# RS232_IrDA.net
KiCad netlist of a schematic drawn in Altium Designer
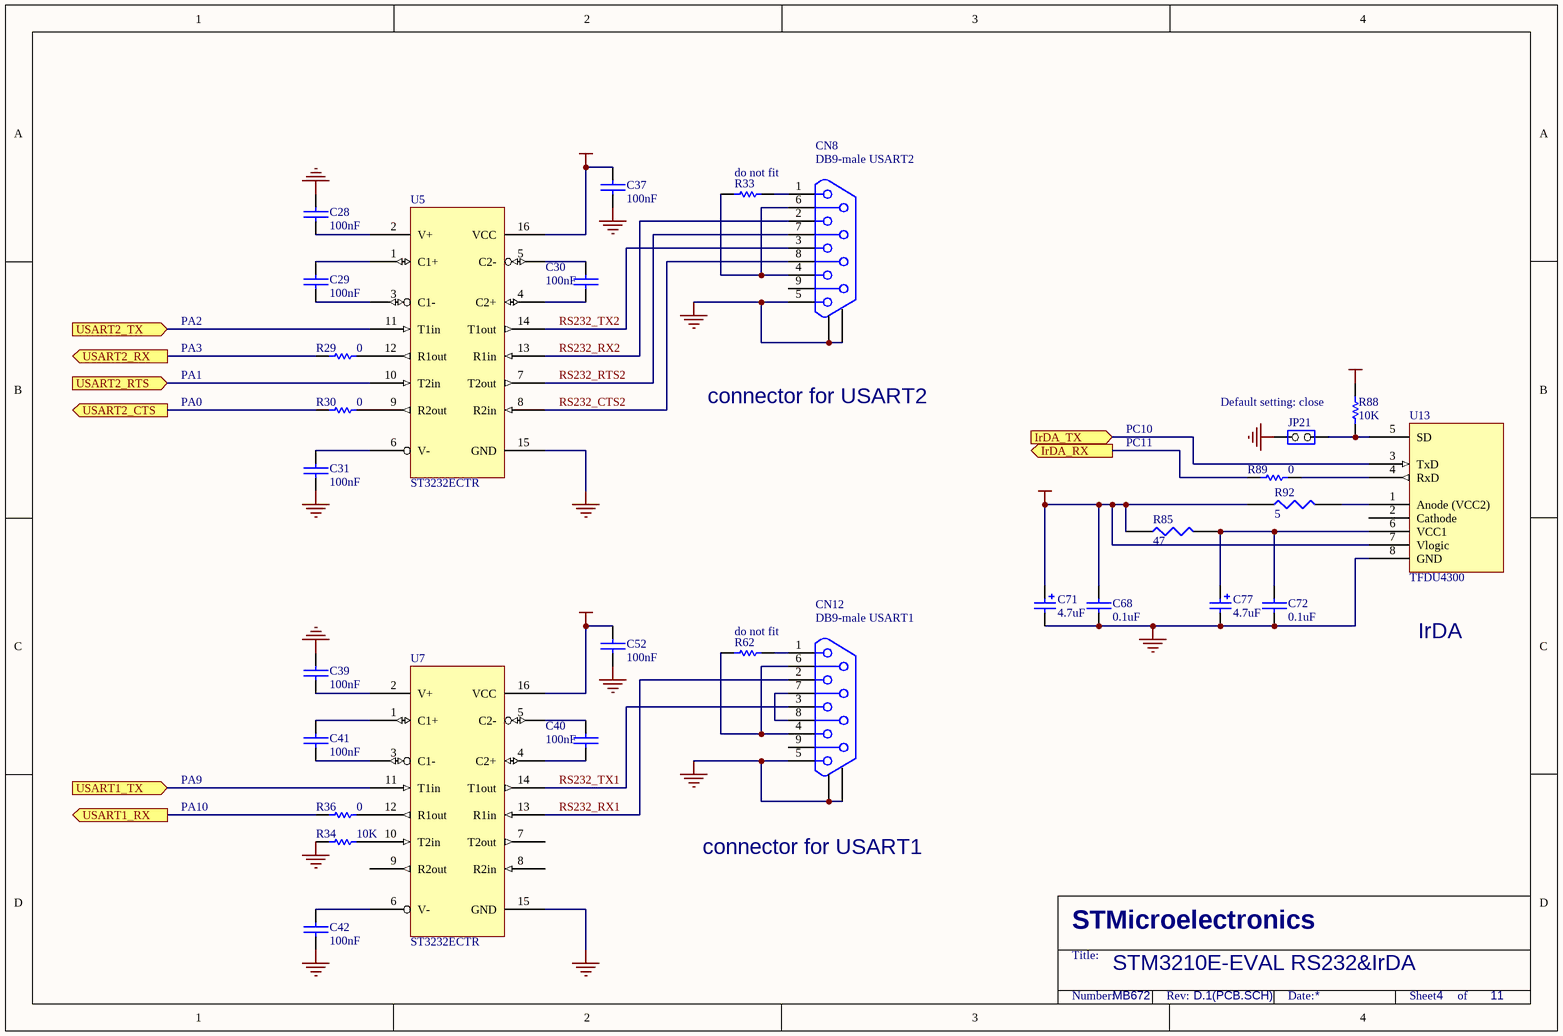
[diagram p0: RS232&IrDA.SchDoc]

(export (version "E")
  (design (tool "Eeschema 10.0.6"))
  (components
    (comp (ref "C28")
      (value "100nF")
      (footprint "0603P")
      (description "Capacitor")
      (libsource (lib "*") (part "CAP"))
    )
    (comp (ref "C29")
      (value "100nF")
      (footprint "0603P")
      (description "Capacitor")
      (libsource (lib "*") (part "CAP"))
    )
    (comp (ref "C30")
      (value "100nF")
      (footprint "0603P")
      (description "Capacitor")
      (libsource (lib "*") (part "CAP"))
    )
    (comp (ref "C31")
      (value "100nF")
      (footprint "0603P")
      (description "Capacitor")
      (libsource (lib "*") (part "CAP"))
    )
    (comp (ref "C37")
      (value "100nF")
      (footprint "0603P")
      (description "Capacitor")
      (libsource (lib "*") (part "CAP"))
    )
    (comp (ref "C39")
      (value "100nF")
      (footprint "0603P")
      (description "Capacitor")
      (libsource (lib "*") (part "CAP"))
    )
    (comp (ref "C40")
      (value "100nF")
      (footprint "0603P")
      (description "Capacitor")
      (libsource (lib "*") (part "CAP"))
    )
    (comp (ref "C41")
      (value "100nF")
      (footprint "0603P")
      (description "Capacitor")
      (libsource (lib "*") (part "CAP"))
    )
    (comp (ref "C42")
      (value "100nF")
      (footprint "0603P")
      (description "Capacitor")
      (libsource (lib "*") (part "CAP"))
    )
    (comp (ref "C52")
      (value "100nF")
      (footprint "0603P")
      (description "Capacitor")
      (libsource (lib "*") (part "CAP"))
    )
    (comp (ref "C68")
      (value "0.1uF")
      (footprint "0603P")
      (description "Capacitor")
      (libsource (lib "*") (part "CAP"))
    )
    (comp (ref "C71")
      (value "4.7uF")
      (footprint "TAN-B")
      (description "Polarized Capacitor (Radial)")
      (fields (field (name "PUBLISHER") "Altium Limited"))
      (libsource (lib "Miscellaneous Devices") (part "Cap Pol1"))
    )
    (comp (ref "C72")
      (value "0.1uF")
      (footprint "0603P")
      (description "Capacitor")
      (libsource (lib "*") (part "CAP"))
    )
    (comp (ref "C77")
      (value "4.7uF")
      (footprint "TAN-B")
      (description "Polarized Capacitor (Radial)")
      (fields (field (name "PUBLISHER") "Altium Limited"))
      (libsource (lib "Miscellaneous Devices") (part "Cap Pol1"))
    )
    (comp (ref "CN8") (value "DB9-male USART2") (footprint "DB9/M") (libsource (lib "*") (part "DB9")))
    (comp (ref "CN12") (value "DB9-male USART1") (footprint "DB9/M") (libsource (lib "*") (part "DB9")))
    (comp (ref "JP21") (value "~") (footprint "SIP2") (libsource (lib "*") (part "JP2")))
    (comp (ref "R29")
      (value "0")
      (description "Resistor")
      (fields (field (name "PUBLISHER") "Altium Limited"))
      (libsource (lib "Miscellaneous Devices") (part "Res1"))
    )
    (comp (ref "R30")
      (value "0")
      (description "Resistor")
      (fields (field (name "PUBLISHER") "Altium Limited"))
      (libsource (lib "Miscellaneous Devices") (part "Res1"))
    )
    (comp (ref "R33")
      (value "do not fit")
      (footprint "0603_NC")
      (description "Resistor")
      (fields (field (name "PUBLISHER") "Altium Limited"))
      (libsource (lib "Miscellaneous Devices") (part "res1"))
    )
    (comp (ref "R34")
      (value "10K")
      (description "Resistor")
      (fields (field (name "PUBLISHER") "Altium Limited"))
      (libsource (lib "Miscellaneous Devices") (part "Res1"))
    )
    (comp (ref "R36")
      (value "0")
      (description "Resistor")
      (fields (field (name "PUBLISHER") "Altium Limited"))
      (libsource (lib "Miscellaneous Devices") (part "Res1"))
    )
    (comp (ref "R62")
      (value "do not fit")
      (footprint "0603_NC")
      (description "Resistor")
      (fields (field (name "PUBLISHER") "Altium Limited"))
      (libsource (lib "Miscellaneous Devices") (part "res1"))
    )
    (comp (ref "R85") (value "47") (footprint "0603") (libsource (lib "*") (part "RES1")))
    (comp (ref "R88")
      (value "10K")
      (description "Resistor")
      (fields (field (name "PUBLISHER") "Altium Limited"))
      (libsource (lib "Miscellaneous Devices") (part "Res1"))
    )
    (comp (ref "R89")
      (value "0")
      (description "Resistor")
      (fields (field (name "PUBLISHER") "Altium Limited"))
      (libsource (lib "Miscellaneous Devices") (part "Res1"))
    )
    (comp (ref "R92") (value "5") (footprint "0603") (libsource (lib "*") (part "RES1")))
    (comp (ref "U5")
      (value "ST3232ECTR")
      (footprint "TSSOP16")
      (description "3.3V/5V Dual RS232 Transceiver w/ Int. Cap.")
      (libsource (lib "*") (part "ST3232"))
    )
    (comp (ref "U7")
      (value "ST3232ECTR")
      (footprint "TSSOP16")
      (description "3.3V/5V Dual RS232 Transceiver w/ Int. Cap.")
      (libsource (lib "*") (part "ST3232"))
    )
    (comp (ref "U13") (value "TFDU4300") (footprint "IR_VISHAY3") (libsource (lib "*") (part "TFDU4300")))
  )
  (nets
    (net (code "1") (name "+3V3") (class "Default")
      (node (ref "C37") (pin "1") (pinfunction "1_1") (pintype "passive"))
      (node (ref "C52") (pin "1") (pinfunction "1_1") (pintype "passive"))
      (node (ref "C68") (pin "1") (pinfunction "1_1") (pintype "passive"))
      (node (ref "C71") (pin "1") (pinfunction "1_1") (pintype "passive"))
      (node (ref "R85") (pin "1") (pinfunction "1_1") (pintype "passive"))
      (node (ref "R88") (pin "2") (pinfunction "2_2") (pintype "passive"))
      (node (ref "R92") (pin "1") (pinfunction "1_1") (pintype "passive"))
      (node (ref "U13") (pin "7") (pinfunction "Vlogic_7") (pintype "passive"))
      (node (ref "U5") (pin "16") (pinfunction "VCC_16") (pintype "passive"))
      (node (ref "U7") (pin "16") (pinfunction "VCC_16") (pintype "passive"))
    )
    (net (code "2") (name "/IrDA_RX") (class "Default")
      (node (ref "R89") (pin "2") (pinfunction "2_2") (pintype "passive"))
    )
    (net (code "3") (name "/IrDA_TX") (class "Default")
      (node (ref "U13") (pin "3") (pinfunction "TxD_3") (pintype "input"))
    )
    (net (code "4") (name "/RS232_CTS2") (class "Default")
      (node (ref "CN8") (pin "8") (pinfunction "8_8") (pintype "passive"))
      (node (ref "U5") (pin "8") (pinfunction "R2in_8") (pintype "input"))
    )
    (net (code "5") (name "/RS232_RTS2") (class "Default")
      (node (ref "CN8") (pin "7") (pinfunction "7_7") (pintype "passive"))
      (node (ref "U5") (pin "7") (pinfunction "T2out_7") (pintype "output"))
    )
    (net (code "6") (name "/RS232_RX1") (class "Default")
      (node (ref "CN12") (pin "2") (pinfunction "2_2") (pintype "passive"))
      (node (ref "U7") (pin "13") (pinfunction "R1in_13") (pintype "input"))
    )
    (net (code "7") (name "/RS232_RX2") (class "Default")
      (node (ref "CN8") (pin "2") (pinfunction "2_2") (pintype "passive"))
      (node (ref "U5") (pin "13") (pinfunction "R1in_13") (pintype "input"))
    )
    (net (code "8") (name "/RS232_TX1") (class "Default")
      (node (ref "CN12") (pin "3") (pinfunction "3_3") (pintype "passive"))
      (node (ref "U7") (pin "14") (pinfunction "T1out_14") (pintype "output"))
    )
    (net (code "9") (name "/RS232_TX2") (class "Default")
      (node (ref "CN8") (pin "3") (pinfunction "3_3") (pintype "passive"))
      (node (ref "U5") (pin "14") (pinfunction "T1out_14") (pintype "output"))
    )
    (net (code "10") (name "/USART1_RX") (class "Default")
      (node (ref "R36") (pin "2") (pinfunction "2_2") (pintype "passive"))
    )
    (net (code "11") (name "/USART1_TX") (class "Default")
      (node (ref "U7") (pin "11") (pinfunction "T1in_11") (pintype "input"))
    )
    (net (code "12") (name "/USART2_CTS") (class "Default")
      (node (ref "R30") (pin "2") (pinfunction "2_2") (pintype "passive"))
    )
    (net (code "13") (name "/USART2_RTS") (class "Default")
      (node (ref "U5") (pin "10") (pinfunction "T2in_10") (pintype "input"))
    )
    (net (code "14") (name "/USART2_RX") (class "Default")
      (node (ref "R29") (pin "2") (pinfunction "2_2") (pintype "passive"))
    )
    (net (code "15") (name "/USART2_TX") (class "Default")
      (node (ref "U5") (pin "11") (pinfunction "T1in_11") (pintype "input"))
    )
    (net (code "16") (name "GND") (class "Default")
      (node (ref "C28") (pin "1") (pinfunction "1_1") (pintype "passive"))
      (node (ref "C31") (pin "1") (pinfunction "1_1") (pintype "passive"))
      (node (ref "C37") (pin "2") (pinfunction "2_2") (pintype "passive"))
      (node (ref "C39") (pin "1") (pinfunction "1_1") (pintype "passive"))
      (node (ref "C42") (pin "1") (pinfunction "1_1") (pintype "passive"))
      (node (ref "C52") (pin "2") (pinfunction "2_2") (pintype "passive"))
      (node (ref "C68") (pin "2") (pinfunction "2_2") (pintype "passive"))
      (node (ref "C71") (pin "2") (pinfunction "2_2") (pintype "passive"))
      (node (ref "C72") (pin "2") (pinfunction "2_2") (pintype "passive"))
      (node (ref "C77") (pin "2") (pinfunction "2_2") (pintype "passive"))
      (node (ref "CN12") (pin "0") (pinfunction "10_0") (pintype "passive"))
      (node (ref "CN12") (pin "5") (pinfunction "5_5") (pintype "passive"))
      (node (ref "CN8") (pin "0") (pinfunction "10_0") (pintype "passive"))
      (node (ref "CN8") (pin "5") (pinfunction "5_5") (pintype "passive"))
      (node (ref "JP21") (pin "2") (pinfunction "NO_2") (pintype "passive"))
      (node (ref "R34") (pin "2") (pinfunction "2_2") (pintype "passive"))
      (node (ref "U13") (pin "8") (pinfunction "GND_8") (pintype "passive"))
      (node (ref "U5") (pin "15") (pinfunction "GND_15") (pintype "passive"))
      (node (ref "U7") (pin "15") (pinfunction "GND_15") (pintype "passive"))
    )
    (net (code "17") (name "Net-(CN8-Pad1)") (class "Default")
      (node (ref "CN8") (pin "1") (pinfunction "1_1") (pintype "passive"))
      (node (ref "R33") (pin "2") (pinfunction "2_2") (pintype "passive"))
    )
    (net (code "18") (name "Net-(CN8-Pad4)") (class "Default")
      (node (ref "CN8") (pin "4") (pinfunction "4_4") (pintype "passive"))
      (node (ref "CN8") (pin "6") (pinfunction "6_6") (pintype "passive"))
      (node (ref "R33") (pin "1") (pinfunction "1_1") (pintype "passive"))
    )
    (net (code "19") (name "Net-(CN12-Pad1)") (class "Default")
      (node (ref "CN12") (pin "1") (pinfunction "1_1") (pintype "passive"))
      (node (ref "R62") (pin "2") (pinfunction "2_2") (pintype "passive"))
    )
    (net (code "20") (name "Net-(CN12-Pad4)") (class "Default")
      (node (ref "CN12") (pin "4") (pinfunction "4_4") (pintype "passive"))
      (node (ref "CN12") (pin "6") (pinfunction "6_6") (pintype "passive"))
      (node (ref "R62") (pin "1") (pinfunction "1_1") (pintype "passive"))
    )
    (net (code "21") (name "Net-(CN12-Pad7)") (class "Default")
      (node (ref "CN12") (pin "7") (pinfunction "7_7") (pintype "passive"))
      (node (ref "CN12") (pin "8") (pinfunction "8_8") (pintype "passive"))
    )
    (net (code "22") (name "Net-(JP21-COMMON)") (class "Default")
      (node (ref "JP21") (pin "1") (pinfunction "COMMON_1") (pintype "passive"))
      (node (ref "R88") (pin "1") (pinfunction "1_1") (pintype "passive"))
      (node (ref "U13") (pin "5") (pinfunction "SD_5") (pintype "passive"))
    )
    (net (code "23") (name "Net-(U5-C1+)") (class "Default")
      (node (ref "C29") (pin "1") (pinfunction "1_1") (pintype "passive"))
      (node (ref "U5") (pin "1") (pinfunction "C1+_1") (pintype "bidirectional"))
    )
    (net (code "24") (name "Net-(U5-C1-)") (class "Default")
      (node (ref "C29") (pin "2") (pinfunction "2_2") (pintype "passive"))
      (node (ref "U5") (pin "3") (pinfunction "C1-_3") (pintype "bidirectional"))
    )
    (net (code "25") (name "Net-(U5-C2+)") (class "Default")
      (node (ref "C30") (pin "1") (pinfunction "1_1") (pintype "passive"))
      (node (ref "U5") (pin "4") (pinfunction "C2+_4") (pintype "bidirectional"))
    )
    (net (code "26") (name "Net-(U5-C2-)") (class "Default")
      (node (ref "C30") (pin "2") (pinfunction "2_2") (pintype "passive"))
      (node (ref "U5") (pin "5") (pinfunction "C2-_5") (pintype "bidirectional"))
    )
    (net (code "27") (name "Net-(U5-R1out)") (class "Default")
      (node (ref "R29") (pin "1") (pinfunction "1_1") (pintype "passive"))
      (node (ref "U5") (pin "12") (pinfunction "R1out_12") (pintype "output"))
    )
    (net (code "28") (name "Net-(U5-R2out)") (class "Default")
      (node (ref "R30") (pin "1") (pinfunction "1_1") (pintype "passive"))
      (node (ref "U5") (pin "9") (pinfunction "R2out_9") (pintype "output"))
    )
    (net (code "29") (name "Net-(U5-V+)") (class "Default")
      (node (ref "C28") (pin "2") (pinfunction "2_2") (pintype "passive"))
      (node (ref "U5") (pin "2") (pinfunction "V+_2") (pintype "passive"))
    )
    (net (code "30") (name "Net-(U5-V-)") (class "Default")
      (node (ref "C31") (pin "2") (pinfunction "2_2") (pintype "passive"))
      (node (ref "U5") (pin "6") (pinfunction "V-_6") (pintype "passive"))
    )
    (net (code "31") (name "Net-(U7-C1+)") (class "Default")
      (node (ref "C41") (pin "1") (pinfunction "1_1") (pintype "passive"))
      (node (ref "U7") (pin "1") (pinfunction "C1+_1") (pintype "bidirectional"))
    )
    (net (code "32") (name "Net-(U7-C1-)") (class "Default")
      (node (ref "C41") (pin "2") (pinfunction "2_2") (pintype "passive"))
      (node (ref "U7") (pin "3") (pinfunction "C1-_3") (pintype "bidirectional"))
    )
    (net (code "33") (name "Net-(U7-C2+)") (class "Default")
      (node (ref "C40") (pin "1") (pinfunction "1_1") (pintype "passive"))
      (node (ref "U7") (pin "4") (pinfunction "C2+_4") (pintype "bidirectional"))
    )
    (net (code "34") (name "Net-(U7-C2-)") (class "Default")
      (node (ref "C40") (pin "2") (pinfunction "2_2") (pintype "passive"))
      (node (ref "U7") (pin "5") (pinfunction "C2-_5") (pintype "bidirectional"))
    )
    (net (code "35") (name "Net-(U7-R1out)") (class "Default")
      (node (ref "R36") (pin "1") (pinfunction "1_1") (pintype "passive"))
      (node (ref "U7") (pin "12") (pinfunction "R1out_12") (pintype "output"))
    )
    (net (code "36") (name "Net-(U7-T2in)") (class "Default")
      (node (ref "R34") (pin "1") (pinfunction "1_1") (pintype "passive"))
      (node (ref "U7") (pin "10") (pinfunction "T2in_10") (pintype "input"))
    )
    (net (code "37") (name "Net-(U7-V+)") (class "Default")
      (node (ref "C39") (pin "2") (pinfunction "2_2") (pintype "passive"))
      (node (ref "U7") (pin "2") (pinfunction "V+_2") (pintype "passive"))
    )
    (net (code "38") (name "Net-(U7-V-)") (class "Default")
      (node (ref "C42") (pin "2") (pinfunction "2_2") (pintype "passive"))
      (node (ref "U7") (pin "6") (pinfunction "V-_6") (pintype "passive"))
    )
    (net (code "39") (name "Net-(U13-Anode_(VCC2))") (class "Default")
      (node (ref "R92") (pin "2") (pinfunction "2_2") (pintype "passive"))
      (node (ref "U13") (pin "1") (pinfunction "Anode_(VCC2)_1") (pintype "passive"))
    )
    (net (code "40") (name "Net-(U13-RxD)") (class "Default")
      (node (ref "R89") (pin "1") (pinfunction "1_1") (pintype "passive"))
      (node (ref "U13") (pin "4") (pinfunction "RxD_4") (pintype "output"))
    )
    (net (code "41") (name "Net-(U13-VCC1)") (class "Default")
      (node (ref "C72") (pin "1") (pinfunction "1_1") (pintype "passive"))
      (node (ref "C77") (pin "1") (pinfunction "1_1") (pintype "passive"))
      (node (ref "R85") (pin "2") (pinfunction "2_2") (pintype "passive"))
      (node (ref "U13") (pin "6") (pinfunction "VCC1_6") (pintype "passive"))
    )
    (net (code "42") (name "unconnected-(CN8-Pad9)") (class "Default")
      (node (ref "CN8") (pin "9") (pinfunction "9_9") (pintype "passive"))
    )
    (net (code "43") (name "unconnected-(CN12-Pad9)") (class "Default")
      (node (ref "CN12") (pin "9") (pinfunction "9_9") (pintype "passive"))
    )
    (net (code "44") (name "unconnected-(U7-R2in-Pad8)") (class "Default")
      (node (ref "U7") (pin "8") (pinfunction "R2in_8") (pintype "input"))
    )
    (net (code "45") (name "unconnected-(U7-R2out-Pad9)") (class "Default")
      (node (ref "U7") (pin "9") (pinfunction "R2out_9") (pintype "output"))
    )
    (net (code "46") (name "unconnected-(U7-T2out-Pad7)") (class "Default")
      (node (ref "U7") (pin "7") (pinfunction "T2out_7") (pintype "output"))
    )
    (net (code "47") (name "unconnected-(U13-Cathode-Pad2)") (class "Default")
      (node (ref "U13") (pin "2") (pinfunction "Cathode_2") (pintype "passive"))
    )
  )
)
